# Sheet1.net
KiCad netlist of a schematic drawn in Altium Designer
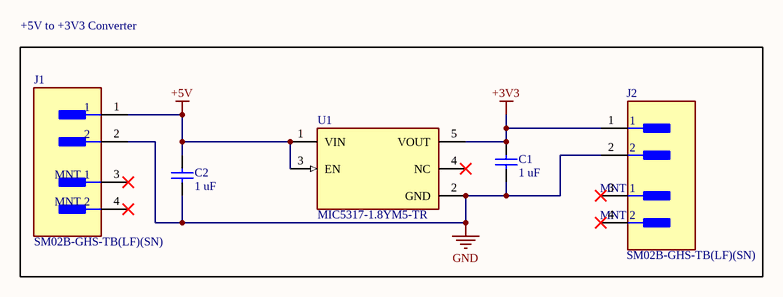
[diagram p0: Sheet1.SchDoc]

(export (version "E")
  (design (tool "Eeschema 10.0.6"))
  (components
    (comp (ref "C1")
      (value "1 uF")
      (footprint "CAPC2013X145X50ML20T25")
      (fields (field (name "PART NUMBER") "C0805C105K8NACTU") (field (name "MANUFACTURER") "Kemet"))
      (libsource (lib "Altium Content Vault") (part "CAP"))
    )
    (comp (ref "C2")
      (value "1 uF")
      (footprint "CAPC2013X145X50ML20T25")
      (fields (field (name "PART NUMBER") "C0805C105K8NACTU") (field (name "MANUFACTURER") "Kemet"))
      (libsource (lib "Altium Content Vault") (part "CAP"))
    )
    (comp (ref "J1")
      (value "SM02B-GHS-TB(LF)(SN)")
      (footprint "FP-SM02B-GHS-TB_LF_SN-MFG")
      (description "CONN HEADER SMD R/A 2POS 1.25MM")
      (libsource (lib "") (part "56ec3178a87b3978bdc1b3682cd516a_1"))
    )
    (comp (ref "J2")
      (value "SM02B-GHS-TB(LF)(SN)")
      (footprint "FP-SM02B-GHS-TB_LF_SN-MFG")
      (description "CONN HEADER SMD R/A 2POS 1.25MM")
      (libsource (lib "Altium Content Vault") (part "56ec3178a87b3978bdc1b3682cd516a"))
    )
    (comp (ref "U1")
      (value "MIC5317-1.8YM5-TR")
      (footprint "FP-SOT23-5LD-PL-1-MFG")
      (description "MIC5317-1.8YM5-TR LDO Regulator Pos 1.8V 0.15A 5-Pin SOT-23 T/R")
      (libsource (lib "Altium Content Vault") (part "ffa7970afa5bd4475d63c28c55078a9"))
    )
  )
  (nets
    (net (code "1") (name "+3V3") (class "Default")
      (node (ref "C1") (pin "2") (pinfunction "2_2") (pintype "passive"))
      (node (ref "J2") (pin "1") (pinfunction "1_1") (pintype "passive"))
      (node (ref "U1") (pin "5") (pinfunction "VOUT_5") (pintype "power_in"))
    )
    (net (code "2") (name "+5V") (class "Default")
      (node (ref "C2") (pin "2") (pinfunction "2_2") (pintype "passive"))
      (node (ref "J1") (pin "1") (pinfunction "1_1") (pintype "passive"))
      (node (ref "U1") (pin "1") (pinfunction "VIN_1") (pintype "power_in"))
      (node (ref "U1") (pin "3") (pinfunction "EN_3") (pintype "input"))
    )
    (net (code "3") (name "GND") (class "Default")
      (node (ref "C1") (pin "1") (pinfunction "1_1") (pintype "passive"))
      (node (ref "C2") (pin "1") (pinfunction "1_1") (pintype "passive"))
      (node (ref "J1") (pin "2") (pinfunction "2_2") (pintype "passive"))
      (node (ref "J2") (pin "2") (pinfunction "2_2") (pintype "passive"))
      (node (ref "U1") (pin "2") (pinfunction "GND_2") (pintype "power_in"))
    )
    (net (code "4") (name "unconnected-(J1-MNT_1-Pad3)") (class "Default")
      (node (ref "J1") (pin "3") (pinfunction "MNT_1_3") (pintype "passive+no_connect"))
    )
    (net (code "5") (name "unconnected-(J1-MNT_2-Pad4)") (class "Default")
      (node (ref "J1") (pin "4") (pinfunction "MNT_2_4") (pintype "passive+no_connect"))
    )
    (net (code "6") (name "unconnected-(J2-MNT_1-Pad3)") (class "Default")
      (node (ref "J2") (pin "3") (pinfunction "MNT_1_3") (pintype "passive+no_connect"))
    )
    (net (code "7") (name "unconnected-(J2-MNT_2-Pad4)") (class "Default")
      (node (ref "J2") (pin "4") (pinfunction "MNT_2_4") (pintype "passive+no_connect"))
    )
    (net (code "8") (name "unconnected-(U1-NC-Pad4)") (class "Default")
      (node (ref "U1") (pin "4") (pinfunction "NC_4") (pintype "passive+no_connect"))
    )
  )
)
